# monitor-board.net
KiCad netlist of a schematic drawn in EAGLE
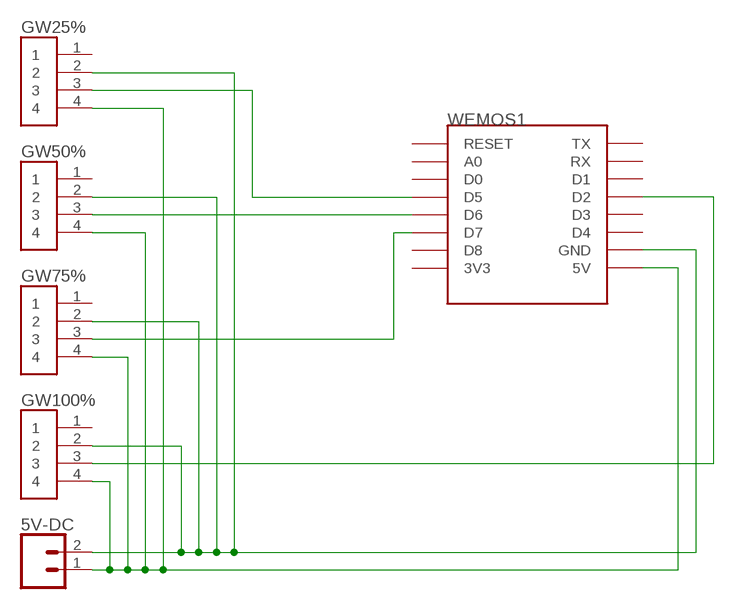
[diagram p0: schematic, sheet 1]

(export (version "E")
  (design (tool "Eeschema 10.0.6"))
  (components
    (comp (ref "5V-DC")
      (value "CONN_02")
      (footprint "eagle-import:1X02")
      (libsource (lib "eagle-import") (part "CONN_02"))
    )
    (comp (ref "GW25%")
      (value "B4B-XH-A(LF)(SN)")
      (footprint "eagle-import:JST_B4B-XH-A(LF)(SN)")
      (fields
        (field (name "DIGI-KEY_PART_NUMBER") "455-2249-ND")
        (field (name "MF") "JST Sales")
        (field (name "MP") "B4B-XH-A_LF__SN_")
      )
      (libsource (lib "eagle-import") (part "B4B-XH-A(LF)(SN)"))
    )
    (comp (ref "GW50%")
      (value "B4B-XH-A(LF)(SN)")
      (footprint "eagle-import:JST_B4B-XH-A(LF)(SN)")
      (fields
        (field (name "DIGI-KEY_PART_NUMBER") "455-2249-ND")
        (field (name "MF") "JST Sales")
        (field (name "MP") "B4B-XH-A_LF__SN_")
      )
      (libsource (lib "eagle-import") (part "B4B-XH-A(LF)(SN)"))
    )
    (comp (ref "GW75%")
      (value "B4B-XH-A(LF)(SN)")
      (footprint "eagle-import:JST_B4B-XH-A(LF)(SN)")
      (fields
        (field (name "DIGI-KEY_PART_NUMBER") "455-2249-ND")
        (field (name "MF") "JST Sales")
        (field (name "MP") "B4B-XH-A_LF__SN_")
      )
      (libsource (lib "eagle-import") (part "B4B-XH-A(LF)(SN)"))
    )
    (comp (ref "GW100%")
      (value "B4B-XH-A(LF)(SN)")
      (footprint "eagle-import:JST_B4B-XH-A(LF)(SN)")
      (fields
        (field (name "DIGI-KEY_PART_NUMBER") "455-2249-ND")
        (field (name "MF") "JST Sales")
        (field (name "MP") "B4B-XH-A_LF__SN_")
      )
      (libsource (lib "eagle-import") (part "B4B-XH-A(LF)(SN)"))
    )
    (comp (ref "WEMOS1")
      (value "WEMOS-D1-MINI")
      (footprint "eagle-import:WEMOS-D1-MINI")
      (libsource (lib "eagle-import") (part "WEMOS-D1-MINI"))
    )
  )
  (nets
    (net (code "1") (name "Net-(5V-DC-Pad1)") (class "Default")
      (node (ref "5V-DC") (pin "1") (pinfunction "1_1") (pintype "passive"))
      (node (ref "GW100%") (pin "4") (pinfunction "4_4") (pintype "passive"))
      (node (ref "GW25%") (pin "4") (pinfunction "4_4") (pintype "passive"))
      (node (ref "GW50%") (pin "4") (pinfunction "4_4") (pintype "passive"))
      (node (ref "GW75%") (pin "4") (pinfunction "4_4") (pintype "passive"))
      (node (ref "WEMOS1") (pin "5V") (pinfunction "5V_5V") (pintype "bidirectional"))
    )
    (net (code "2") (name "Net-(5V-DC-Pad2)") (class "Default")
      (node (ref "5V-DC") (pin "2") (pinfunction "2_2") (pintype "passive"))
      (node (ref "GW100%") (pin "2") (pinfunction "2_2") (pintype "passive"))
      (node (ref "GW25%") (pin "2") (pinfunction "2_2") (pintype "passive"))
      (node (ref "GW50%") (pin "2") (pinfunction "2_2") (pintype "passive"))
      (node (ref "GW75%") (pin "2") (pinfunction "2_2") (pintype "passive"))
      (node (ref "WEMOS1") (pin "GND") (pinfunction "GND_GND") (pintype "bidirectional"))
    )
    (net (code "3") (name "Net-(GW25%-Pad3)") (class "Default")
      (node (ref "GW25%") (pin "3") (pinfunction "3_3") (pintype "passive"))
      (node (ref "WEMOS1") (pin "D5") (pinfunction "D5_D5") (pintype "bidirectional"))
    )
    (net (code "4") (name "Net-(GW50%-Pad3)") (class "Default")
      (node (ref "GW50%") (pin "3") (pinfunction "3_3") (pintype "passive"))
      (node (ref "WEMOS1") (pin "D6") (pinfunction "D6_D6") (pintype "bidirectional"))
    )
    (net (code "5") (name "Net-(GW75%-Pad3)") (class "Default")
      (node (ref "GW75%") (pin "3") (pinfunction "3_3") (pintype "passive"))
      (node (ref "WEMOS1") (pin "D7") (pinfunction "D7_D7") (pintype "bidirectional"))
    )
    (net (code "6") (name "Net-(GW100%-Pad3)") (class "Default")
      (node (ref "GW100%") (pin "3") (pinfunction "3_3") (pintype "passive"))
      (node (ref "WEMOS1") (pin "D2") (pinfunction "D2_D2") (pintype "bidirectional"))
    )
    (net (code "7") (name "unconnected-(GW25%-Pad1)") (class "Default")
      (node (ref "GW25%") (pin "1") (pinfunction "1_1") (pintype "passive"))
    )
    (net (code "8") (name "unconnected-(GW50%-Pad1)") (class "Default")
      (node (ref "GW50%") (pin "1") (pinfunction "1_1") (pintype "passive"))
    )
    (net (code "9") (name "unconnected-(GW75%-Pad1)") (class "Default")
      (node (ref "GW75%") (pin "1") (pinfunction "1_1") (pintype "passive"))
    )
    (net (code "10") (name "unconnected-(GW100%-Pad1)") (class "Default")
      (node (ref "GW100%") (pin "1") (pinfunction "1_1") (pintype "passive"))
    )
    (net (code "11") (name "unconnected-(WEMOS1-Pad3V3)") (class "Default")
      (node (ref "WEMOS1") (pin "3V3") (pinfunction "3V3_3V3") (pintype "bidirectional"))
    )
    (net (code "12") (name "unconnected-(WEMOS1-PadA0)") (class "Default")
      (node (ref "WEMOS1") (pin "A0") (pinfunction "A0_A0") (pintype "bidirectional"))
    )
    (net (code "13") (name "unconnected-(WEMOS1-PadD0)") (class "Default")
      (node (ref "WEMOS1") (pin "D0") (pinfunction "D0_D0") (pintype "bidirectional"))
    )
    (net (code "14") (name "unconnected-(WEMOS1-PadD1)") (class "Default")
      (node (ref "WEMOS1") (pin "D1") (pinfunction "D1_D1") (pintype "bidirectional"))
    )
    (net (code "15") (name "unconnected-(WEMOS1-PadD3)") (class "Default")
      (node (ref "WEMOS1") (pin "D3") (pinfunction "D3_D3") (pintype "bidirectional"))
    )
    (net (code "16") (name "unconnected-(WEMOS1-PadD4)") (class "Default")
      (node (ref "WEMOS1") (pin "D4") (pinfunction "D4_D4") (pintype "bidirectional"))
    )
    (net (code "17") (name "unconnected-(WEMOS1-PadD8)") (class "Default")
      (node (ref "WEMOS1") (pin "D8") (pinfunction "D8_D8") (pintype "bidirectional"))
    )
    (net (code "18") (name "unconnected-(WEMOS1-PadRESET)") (class "Default")
      (node (ref "WEMOS1") (pin "RESET") (pinfunction "RESET_RESET") (pintype "bidirectional"))
    )
    (net (code "19") (name "unconnected-(WEMOS1-PadRX)") (class "Default")
      (node (ref "WEMOS1") (pin "RX") (pinfunction "RX_RX") (pintype "bidirectional"))
    )
    (net (code "20") (name "unconnected-(WEMOS1-PadTX)") (class "Default")
      (node (ref "WEMOS1") (pin "TX") (pinfunction "TX_TX") (pintype "bidirectional"))
    )
  )
)
